# SlimPower.net
KiCad netlist of a schematic drawn in Altium Designer
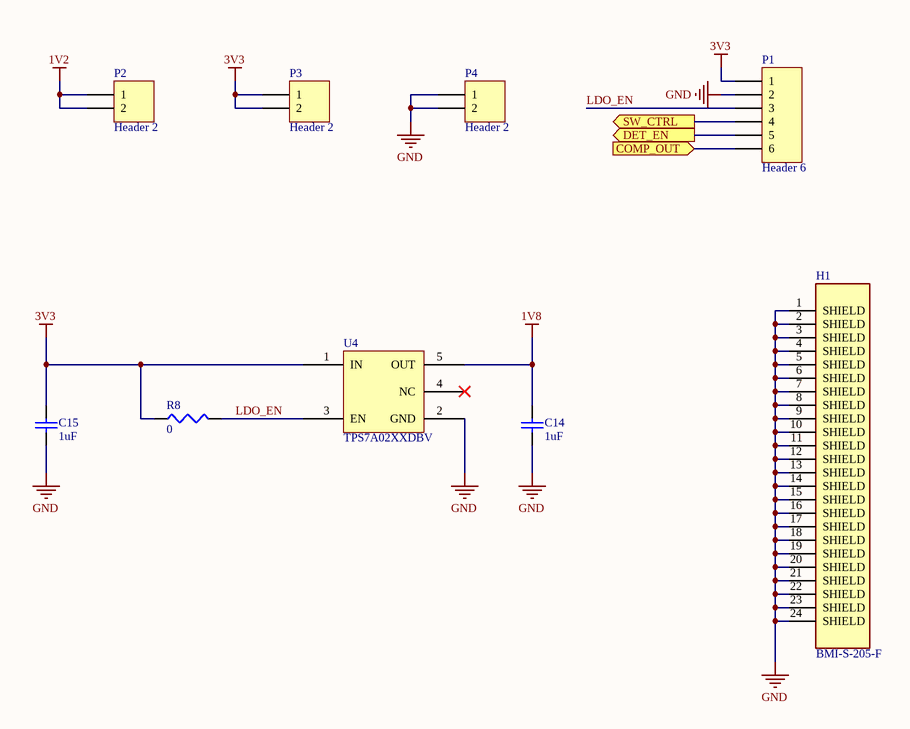
[diagram p0: SlimPower.SchDoc]

(export (version "E")
  (design (tool "Eeschema 10.0.6"))
  (components
    (comp (ref "C14")
      (value "1uF")
      (footprint "SMD-0603")
      (description "Ceramic Capacitor 0603")
      (libsource (lib "LCR") (part "CAP0603"))
    )
    (comp (ref "C15")
      (value "1uF")
      (footprint "SMD-0603")
      (description "Ceramic Capacitor 0603")
      (libsource (lib "LCR") (part "CAP0603"))
    )
    (comp (ref "H1")
      (value "BMI-S-205-F")
      (footprint "LAIRD_BMI-S-205-F")
      (description "RF Shield Frame 1.000 _25.40mm_ X 1.500 _38.10mm_ Solder")
      (fields (field (name "MF") "Laird Technologies"))
      (libsource (lib "BMI-S-205-F") (part "BMI-S-205-F"))
    )
    (comp (ref "P1")
      (value "Header 6")
      (footprint "HDR1X6")
      (description "Header, 6-Pin")
      (fields (field (name "PUBLISHER") "Altium Limited"))
      (libsource (lib "Miscellaneous Connectors") (part "Header 6"))
    )
    (comp (ref "P2")
      (value "Header 2")
      (footprint "HDR1X2")
      (description "Header, 2-Pin")
      (fields (field (name "PUBLISHER") "Altium Limited"))
      (libsource (lib "Miscellaneous Connectors") (part "Header 2"))
    )
    (comp (ref "P3")
      (value "Header 2")
      (footprint "HDR1X2")
      (description "Header, 2-Pin")
      (fields (field (name "PUBLISHER") "Altium Limited"))
      (libsource (lib "Miscellaneous Connectors") (part "Header 2"))
    )
    (comp (ref "P4")
      (value "Header 2")
      (footprint "HDR1X2")
      (description "Header, 2-Pin")
      (fields (field (name "PUBLISHER") "Altium Limited"))
      (libsource (lib "Miscellaneous Connectors") (part "Header 2"))
    )
    (comp (ref "R8")
      (value "0")
      (footprint "SMD-0603")
      (description "Resistor-0603")
      (libsource (lib "LCR") (part "RES0603"))
    )
    (comp (ref "U4")
      (value "TPS7A02XXDBV")
      (footprint "SOT95P280X145-5N")
      (description "TPS7A02 Nanopower IQ, 25-nA, 200-mA, Low-Dropout Voltage Regulator With Fast\r\nTransient Response")
      (libsource (lib "PowerManagement") (part "TPS7A02XXDBV"))
    )
  )
  (nets
    (net (code "1") (name "/COMP_OUT") (class "Default")
      (node (ref "P1") (pin "6") (pinfunction "6_6") (pintype "passive"))
    )
    (net (code "2") (name "/DET_EN") (class "Default")
      (node (ref "P1") (pin "5") (pinfunction "5_5") (pintype "passive"))
    )
    (net (code "3") (name "/LDO_EN") (class "Default")
      (node (ref "P1") (pin "3") (pinfunction "3_3") (pintype "passive"))
      (node (ref "R8") (pin "2") (pinfunction "2_2") (pintype "passive"))
      (node (ref "U4") (pin "3") (pinfunction "EN_3") (pintype "passive"))
    )
    (net (code "4") (name "/SW_CTRL") (class "Default")
      (node (ref "P1") (pin "4") (pinfunction "4_4") (pintype "passive"))
    )
    (net (code "5") (name "1V2") (class "Default")
      (node (ref "P2") (pin "1") (pinfunction "1_1") (pintype "passive"))
      (node (ref "P2") (pin "2") (pinfunction "2_2") (pintype "passive"))
    )
    (net (code "6") (name "1V8") (class "Default")
      (node (ref "C14") (pin "2") (pinfunction "2_2") (pintype "passive"))
      (node (ref "U4") (pin "5") (pinfunction "OUT_5") (pintype "passive"))
    )
    (net (code "7") (name "3V3") (class "Default")
      (node (ref "C15") (pin "2") (pinfunction "2_2") (pintype "passive"))
      (node (ref "P1") (pin "1") (pinfunction "1_1") (pintype "passive"))
      (node (ref "P3") (pin "1") (pinfunction "1_1") (pintype "passive"))
      (node (ref "P3") (pin "2") (pinfunction "2_2") (pintype "passive"))
      (node (ref "R8") (pin "1") (pinfunction "1_1") (pintype "passive"))
      (node (ref "U4") (pin "1") (pinfunction "IN_1") (pintype "passive"))
    )
    (net (code "8") (name "GND") (class "Default")
      (node (ref "C14") (pin "1") (pinfunction "1_1") (pintype "passive"))
      (node (ref "C15") (pin "1") (pinfunction "1_1") (pintype "passive"))
      (node (ref "H1") (pin "1") (pinfunction "SHIELD_1") (pintype "power_in"))
      (node (ref "H1") (pin "10") (pinfunction "SHIELD_10") (pintype "power_in"))
      (node (ref "H1") (pin "11") (pinfunction "SHIELD_11") (pintype "power_in"))
      (node (ref "H1") (pin "12") (pinfunction "SHIELD_12") (pintype "power_in"))
      (node (ref "H1") (pin "13") (pinfunction "SHIELD_13") (pintype "power_in"))
      (node (ref "H1") (pin "14") (pinfunction "SHIELD_14") (pintype "power_in"))
      (node (ref "H1") (pin "15") (pinfunction "SHIELD_15") (pintype "power_in"))
      (node (ref "H1") (pin "16") (pinfunction "SHIELD_16") (pintype "power_in"))
      (node (ref "H1") (pin "17") (pinfunction "SHIELD_17") (pintype "power_in"))
      (node (ref "H1") (pin "18") (pinfunction "SHIELD_18") (pintype "power_in"))
      (node (ref "H1") (pin "19") (pinfunction "SHIELD_19") (pintype "power_in"))
      (node (ref "H1") (pin "2") (pinfunction "SHIELD_2") (pintype "power_in"))
      (node (ref "H1") (pin "20") (pinfunction "SHIELD_20") (pintype "power_in"))
      (node (ref "H1") (pin "21") (pinfunction "SHIELD_21") (pintype "power_in"))
      (node (ref "H1") (pin "22") (pinfunction "SHIELD_22") (pintype "power_in"))
      (node (ref "H1") (pin "23") (pinfunction "SHIELD_23") (pintype "power_in"))
      (node (ref "H1") (pin "24") (pinfunction "SHIELD_24") (pintype "power_in"))
      (node (ref "H1") (pin "3") (pinfunction "SHIELD_3") (pintype "power_in"))
      (node (ref "H1") (pin "4") (pinfunction "SHIELD_4") (pintype "power_in"))
      (node (ref "H1") (pin "5") (pinfunction "SHIELD_5") (pintype "power_in"))
      (node (ref "H1") (pin "6") (pinfunction "SHIELD_6") (pintype "power_in"))
      (node (ref "H1") (pin "7") (pinfunction "SHIELD_7") (pintype "power_in"))
      (node (ref "H1") (pin "8") (pinfunction "SHIELD_8") (pintype "power_in"))
      (node (ref "H1") (pin "9") (pinfunction "SHIELD_9") (pintype "power_in"))
      (node (ref "P1") (pin "2") (pinfunction "2_2") (pintype "passive"))
      (node (ref "P4") (pin "1") (pinfunction "1_1") (pintype "passive"))
      (node (ref "P4") (pin "2") (pinfunction "2_2") (pintype "passive"))
      (node (ref "U4") (pin "2") (pinfunction "GND_2") (pintype "passive"))
    )
    (net (code "9") (name "unconnected-(U4-NC-Pad4)") (class "Default")
      (node (ref "U4") (pin "4") (pinfunction "NC_4") (pintype "passive+no_connect"))
    )
  )
)
